# JacdacRp2040BrainEc30_124.net
KiCad netlist of a schematic drawn in Altium Designer
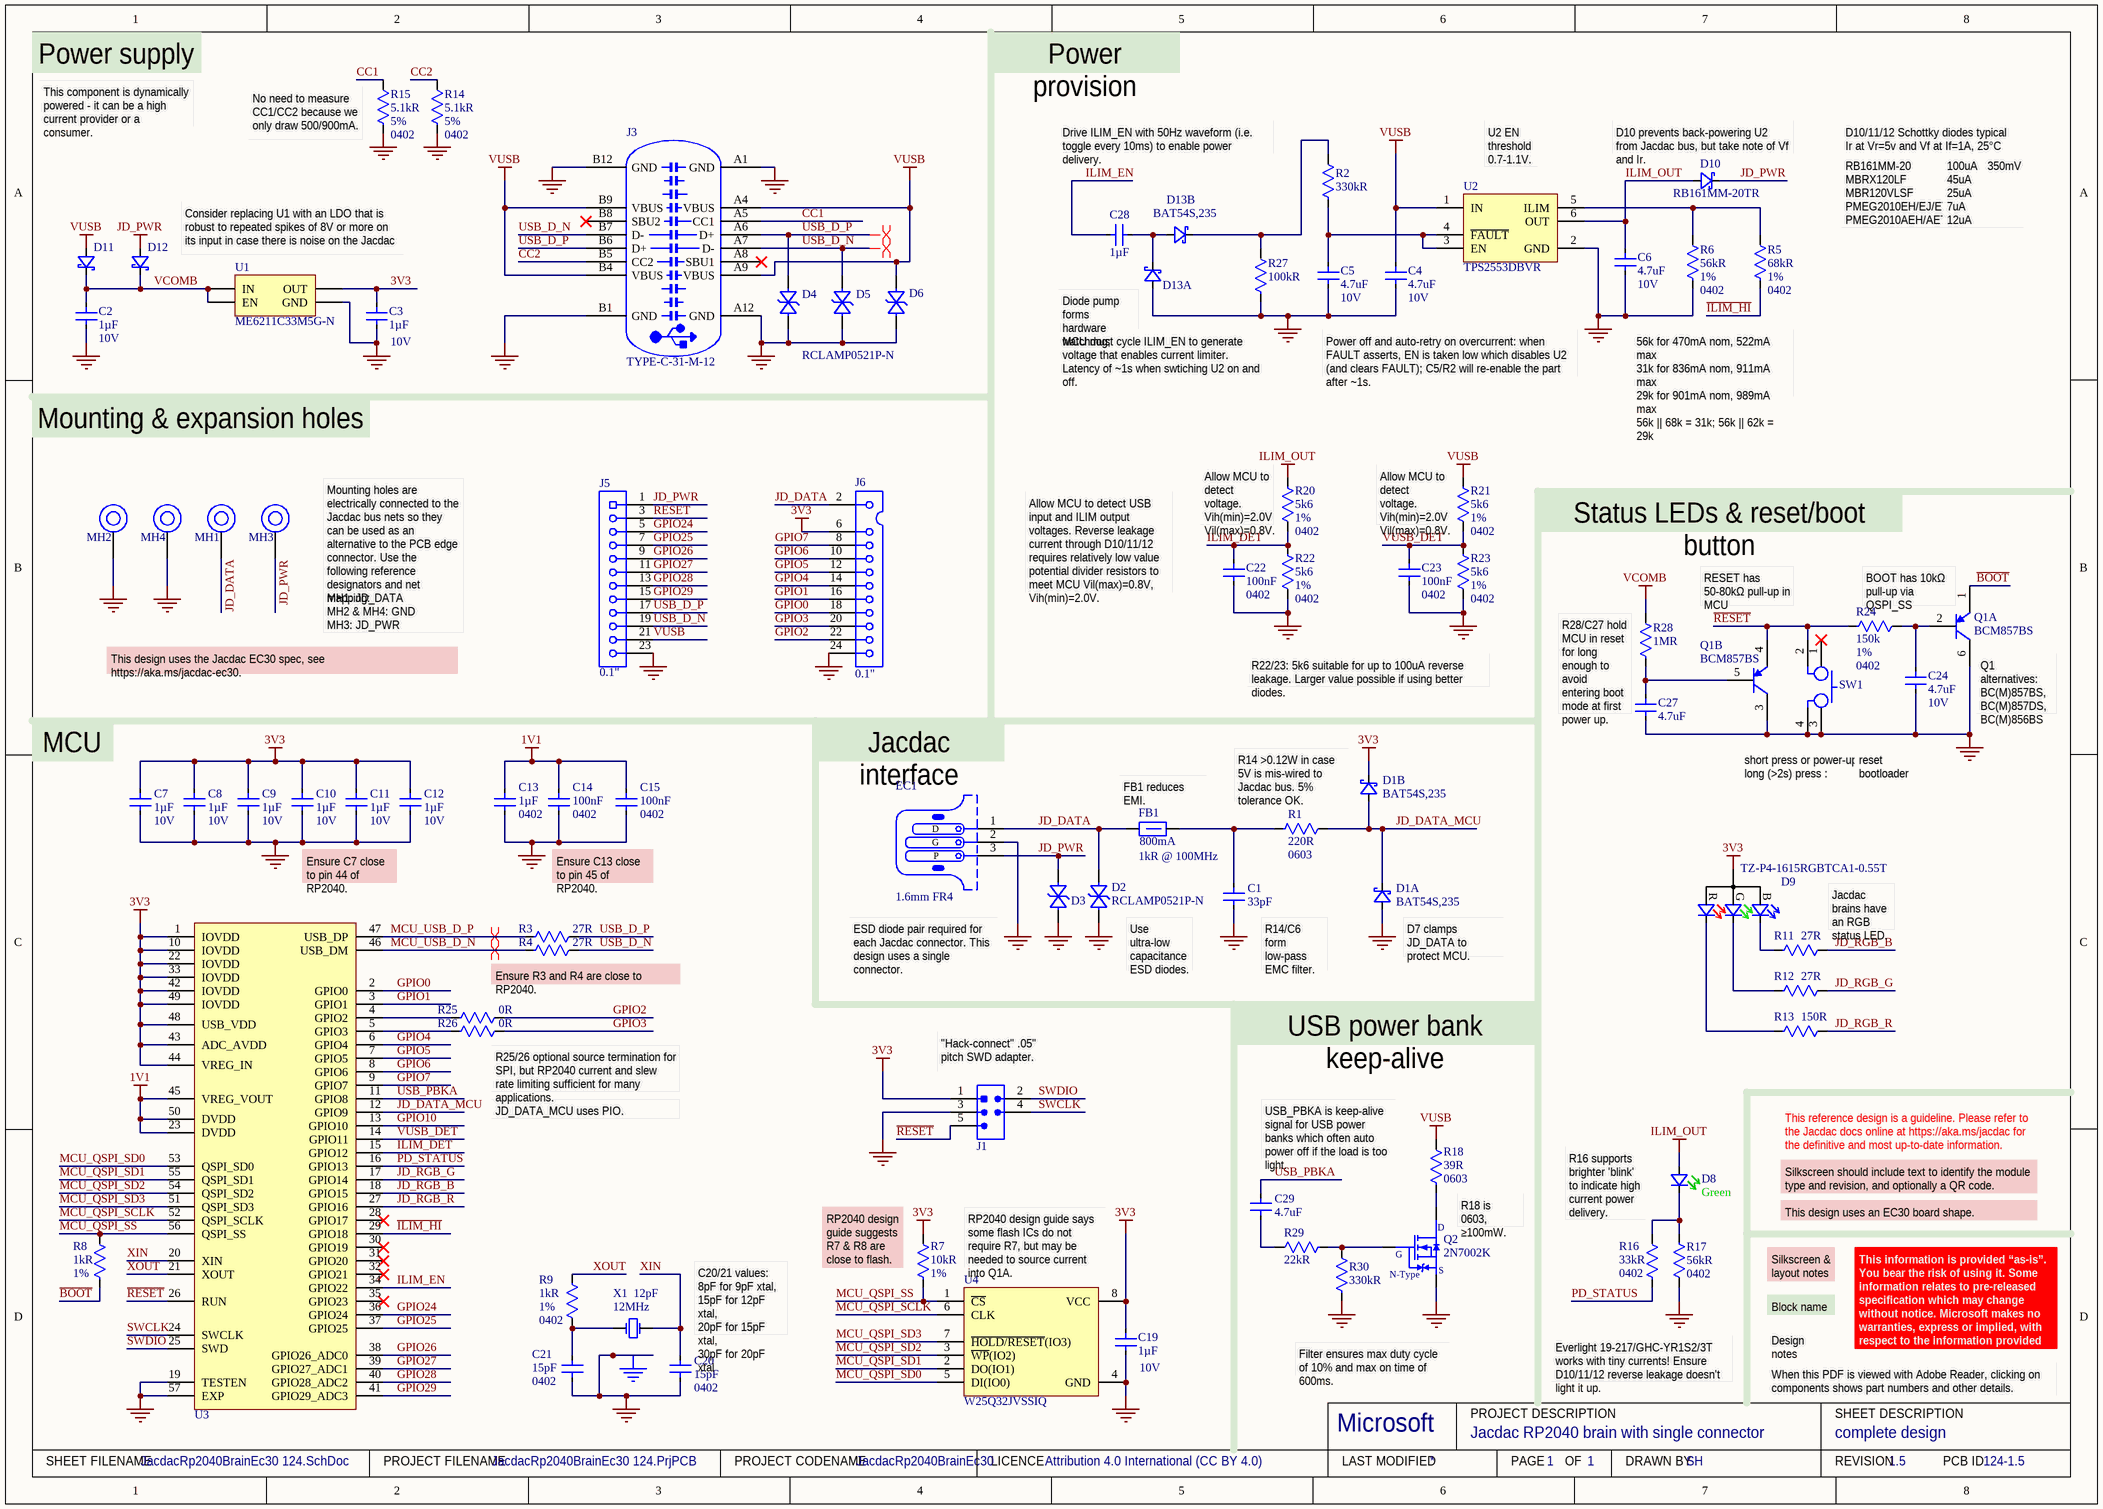
[diagram p0: JacdacRp2040BrainEc30 124.SchDoc]

(export (version "E")
  (design (tool "Eeschema 10.0.6"))
  (components
    (comp (ref "C1")
      (value "CL05C330JB51PNC")
      (footprint "C0402_0.55MM - without outline")
      (description "CAP CER 33PF 50V NP0 0402")
      (fields
        (field (name "MANUFACTURER") "Samsung")
        (field (name "TOLERANCE") "5%")
        (field (name "CAPACITANCE") "33pF")
        (field (name "CHECKED") "?")
        (field (name "CREATED") "DG")
      )
      (libsource (lib "Samsung") (part "CL05C330JB51PNC"))
    )
    (comp (ref "C2")
      (value "CL05A105KP5NNNC")
      (footprint "C0402_0.55MM - without outline")
      (description "CAP CER 1UF 10V X5R 0402")
      (fields
        (field (name "MANUFACTURER") "Samsung")
        (field (name "TOLERANCE") "10%")
        (field (name "CAPACITANCE") "1µF")
        (field (name "VOLTAGE RATING") "10V")
        (field (name "CREATED") "DG")
        (field (name "CHECKED") "?")
      )
      (libsource (lib "Samsung") (part "CL05A105KP5NNNC"))
    )
    (comp (ref "C3")
      (value "CL05A105KP5NNNC")
      (footprint "C0402_0.55MM - without outline")
      (description "CAP CER 1UF 10V X5R 0402")
      (fields
        (field (name "MANUFACTURER") "Samsung")
        (field (name "TOLERANCE") "10%")
        (field (name "CAPACITANCE") "1µF")
        (field (name "VOLTAGE RATING") "10V")
        (field (name "CREATED") "DG")
        (field (name "CHECKED") "?")
      )
      (libsource (lib "Samsung") (part "CL05A105KP5NNNC"))
    )
    (comp (ref "C4")
      (value "CL05A475MP5NRNC")
      (footprint "SAMSUNG-CAP-0402:C0402_0.55mm - without outline")
      (description "CAP CER 4.7UF 10V X5R 0402")
      (fields
        (field (name "MANUFACTURER") "Samsung")
        (field (name "TOLERANCE") "20%")
        (field (name "CAPACITANCE") "4.7uF")
        (field (name "VOLTAGE RATING") "10V")
        (field (name "CREATED BY") "D. Gakure")
        (field (name "CHECKED BY") "?")
      )
      (libsource (lib "Samsung") (part "CL05A475MP5NRNC"))
    )
    (comp (ref "C5")
      (value "CL05A475MP5NRNC")
      (footprint "SAMSUNG-CAP-0402:C0402_0.55mm - without outline")
      (description "CAP CER 4.7UF 10V X5R 0402")
      (fields
        (field (name "MANUFACTURER") "Samsung")
        (field (name "TOLERANCE") "20%")
        (field (name "CAPACITANCE") "4.7uF")
        (field (name "VOLTAGE RATING") "10V")
        (field (name "CREATED BY") "D. Gakure")
        (field (name "CHECKED BY") "?")
      )
      (libsource (lib "Samsung") (part "CL05A475MP5NRNC"))
    )
    (comp (ref "C6")
      (value "CL05A475MP5NRNC")
      (footprint "SAMSUNG-CAP-0402:C0402_0.55mm - without outline")
      (description "CAP CER 4.7UF 10V X5R 0402")
      (fields
        (field (name "MANUFACTURER") "Samsung")
        (field (name "TOLERANCE") "20%")
        (field (name "CAPACITANCE") "4.7uF")
        (field (name "VOLTAGE RATING") "10V")
        (field (name "CREATED BY") "D. Gakure")
        (field (name "CHECKED BY") "?")
      )
      (libsource (lib "Samsung") (part "CL05A475MP5NRNC"))
    )
    (comp (ref "C7")
      (value "CL05A105KP5NNNC")
      (footprint "C0402_0.55MM - without outline")
      (description "CAP CER 1UF 10V X5R 0402")
      (fields
        (field (name "MANUFACTURER") "Samsung")
        (field (name "TOLERANCE") "10%")
        (field (name "CAPACITANCE") "1µF")
        (field (name "VOLTAGE RATING") "10V")
        (field (name "CREATED") "DG")
        (field (name "CHECKED") "?")
      )
      (libsource (lib "Samsung") (part "CL05A105KP5NNNC"))
    )
    (comp (ref "C8")
      (value "CL05A105KP5NNNC")
      (footprint "C0402_0.55MM - without outline")
      (description "CAP CER 1UF 10V X5R 0402")
      (fields
        (field (name "MANUFACTURER") "Samsung")
        (field (name "TOLERANCE") "10%")
        (field (name "CAPACITANCE") "1µF")
        (field (name "VOLTAGE RATING") "10V")
        (field (name "CREATED") "DG")
        (field (name "CHECKED") "?")
      )
      (libsource (lib "Samsung") (part "CL05A105KP5NNNC"))
    )
    (comp (ref "C9")
      (value "CL05A105KP5NNNC")
      (footprint "C0402_0.55MM - without outline")
      (description "CAP CER 1UF 10V X5R 0402")
      (fields
        (field (name "MANUFACTURER") "Samsung")
        (field (name "TOLERANCE") "10%")
        (field (name "CAPACITANCE") "1µF")
        (field (name "VOLTAGE RATING") "10V")
        (field (name "CREATED") "DG")
        (field (name "CHECKED") "?")
      )
      (libsource (lib "Samsung") (part "CL05A105KP5NNNC"))
    )
    (comp (ref "C10")
      (value "CL05A105KP5NNNC")
      (footprint "C0402_0.55MM - without outline")
      (description "CAP CER 1UF 10V X5R 0402")
      (fields
        (field (name "MANUFACTURER") "Samsung")
        (field (name "TOLERANCE") "10%")
        (field (name "CAPACITANCE") "1µF")
        (field (name "VOLTAGE RATING") "10V")
        (field (name "CREATED") "DG")
        (field (name "CHECKED") "?")
      )
      (libsource (lib "Samsung") (part "CL05A105KP5NNNC"))
    )
    (comp (ref "C11")
      (value "CL05A105KP5NNNC")
      (footprint "C0402_0.55MM - without outline")
      (description "CAP CER 1UF 10V X5R 0402")
      (fields
        (field (name "MANUFACTURER") "Samsung")
        (field (name "TOLERANCE") "10%")
        (field (name "CAPACITANCE") "1µF")
        (field (name "VOLTAGE RATING") "10V")
        (field (name "CREATED") "DG")
        (field (name "CHECKED") "?")
      )
      (libsource (lib "Samsung") (part "CL05A105KP5NNNC"))
    )
    (comp (ref "C12")
      (value "CL05A105KP5NNNC")
      (footprint "C0402_0.55MM - without outline")
      (description "CAP CER 1UF 10V X5R 0402")
      (fields
        (field (name "MANUFACTURER") "Samsung")
        (field (name "TOLERANCE") "10%")
        (field (name "CAPACITANCE") "1µF")
        (field (name "VOLTAGE RATING") "10V")
        (field (name "CREATED") "DG")
        (field (name "CHECKED") "?")
      )
      (libsource (lib "Samsung") (part "CL05A105KP5NNNC"))
    )
    (comp (ref "C13")
      (value "CL05A105KP5NNNC")
      (footprint "C0402_0.55MM - without outline")
      (description "CAP CER 1UF 10V X5R 0402")
      (fields
        (field (name "MANUFACTURER") "Samsung")
        (field (name "CASE/PACKAGE") "0402")
        (field (name "TOLERANCE") "10%")
        (field (name "CAPACITANCE") "1µF")
        (field (name "CREATED") "DG")
        (field (name "CHECKED") "?")
      )
      (libsource (lib "Samsung") (part "CL05A105KP5NNNC"))
    )
    (comp (ref "C14")
      (value "CL05B104KP5NNNC")
      (footprint "SAMSUNG-CAP-0402:C0402_0.55MM - without outline")
      (description "CAP CER 0.1UF 10V X7R 0402")
      (fields
        (field (name "MANUFACTURER") "Samsung")
        (field (name "TOLERANCE") "10%")
        (field (name "CAPACITANCE") "100nF")
        (field (name "CASE CODE (IMPERIAL)") "0402")
        (field (name "CREATED") "DG")
        (field (name "CHECKED") "?")
      )
      (libsource (lib "Samsung") (part "CL05B104KP5NNNC"))
    )
    (comp (ref "C15")
      (value "CL05B104KP5NNNC")
      (footprint "SAMSUNG-CAP-0402:C0402_0.55MM - without outline")
      (description "CAP CER 0.1UF 10V X7R 0402")
      (fields
        (field (name "MANUFACTURER") "Samsung")
        (field (name "TOLERANCE") "10%")
        (field (name "CAPACITANCE") "100nF")
        (field (name "CASE CODE (IMPERIAL)") "0402")
        (field (name "CREATED") "DG")
        (field (name "CHECKED") "?")
      )
      (libsource (lib "Samsung") (part "CL05B104KP5NNNC"))
    )
    (comp (ref "C19")
      (value "CL05A105KP5NNNC")
      (footprint "C0402_0.55MM - without outline")
      (description "CAP CER 1UF 10V X5R 0402")
      (fields
        (field (name "MANUFACTURER") "Samsung")
        (field (name "TOLERANCE") "10%")
        (field (name "CAPACITANCE") "1µF")
        (field (name "VOLTAGE RATING") "10V")
        (field (name "CREATED") "DG")
        (field (name "CHECKED") "?")
      )
      (libsource (lib "Samsung") (part "CL05A105KP5NNNC"))
    )
    (comp (ref "C20")
      (value "CL05C150JB5NNNC")
      (footprint "C0402_0.55MM - without outline")
      (description "CAP CER 15PF 50V C0G/NP0 0402")
      (fields
        (field (name "MANUFACTURER") "Samsung")
        (field (name "TOLERANCE") "5%")
        (field (name "CAPACITANCE") "15pF")
        (field (name "CASE/PACKAGE") "0402")
      )
      (libsource (lib "Samsung") (part "CL05C150JB5NNNC"))
    )
    (comp (ref "C21")
      (value "CL05C150JB5NNNC")
      (footprint "C0402_0.55MM - without outline")
      (description "CAP CER 15PF 50V C0G/NP0 0402")
      (fields
        (field (name "MANUFACTURER") "Samsung")
        (field (name "TOLERANCE") "5%")
        (field (name "CAPACITANCE") "15pF")
        (field (name "CASE/PACKAGE") "0402")
      )
      (libsource (lib "Samsung") (part "CL05C150JB5NNNC"))
    )
    (comp (ref "C22")
      (value "CL05B104KP5NNNC")
      (footprint "SAMSUNG-CAP-0402:C0402_0.55MM - without outline")
      (description "CAP CER 0.1UF 10V X7R 0402")
      (fields
        (field (name "MANUFACTURER") "Samsung")
        (field (name "TOLERANCE") "10%")
        (field (name "CAPACITANCE") "100nF")
        (field (name "CASE CODE (IMPERIAL)") "0402")
        (field (name "CREATED") "DG")
        (field (name "CHECKED") "?")
      )
      (libsource (lib "Samsung") (part "CL05B104KP5NNNC"))
    )
    (comp (ref "C23")
      (value "CL05B104KP5NNNC")
      (footprint "SAMSUNG-CAP-0402:C0402_0.55MM - without outline")
      (description "CAP CER 0.1UF 10V X7R 0402")
      (fields
        (field (name "MANUFACTURER") "Samsung")
        (field (name "TOLERANCE") "10%")
        (field (name "CAPACITANCE") "100nF")
        (field (name "CASE CODE (IMPERIAL)") "0402")
        (field (name "CREATED") "DG")
        (field (name "CHECKED") "?")
      )
      (libsource (lib "Samsung") (part "CL05B104KP5NNNC"))
    )
    (comp (ref "C24")
      (value "CL05A475MP5NRNC")
      (footprint "SAMSUNG-CAP-0402:C0402_0.55mm - without outline")
      (description "CAP CER 4.7UF 10V X5R 0402")
      (fields
        (field (name "MANUFACTURER") "Samsung")
        (field (name "TOLERANCE") "20%")
        (field (name "CAPACITANCE") "4.7uF")
        (field (name "VOLTAGE RATING") "10V")
        (field (name "CREATED BY") "D. Gakure")
        (field (name "CHECKED BY") "?")
      )
      (libsource (lib "Samsung") (part "CL05A475MP5NRNC"))
    )
    (comp (ref "C27")
      (value "CL05A475MP5NRNC")
      (footprint "SAMSUNG-CAP-0402:C0402_0.55mm - without outline")
      (description "CAP CER 4.7UF 10V X5R 0402")
      (fields
        (field (name "MANUFACTURER") "Samsung")
        (field (name "TOLERANCE") "20%")
        (field (name "CAPACITANCE") "4.7uF")
        (field (name "CREATED BY") "D. Gakure")
        (field (name "CHECKED BY") "?")
      )
      (libsource (lib "Samsung") (part "CL05A475MP5NRNC"))
    )
    (comp (ref "C28")
      (value "CL05A105KP5NNNC")
      (footprint "SAMSUNG-CAP-0402:C0402_0.55MM - without outline")
      (description "CAP CER 1UF 10V X5R 0402")
      (fields
        (field (name "MANUFACTURER") "Samsung")
        (field (name "TOLERANCE") "10%")
        (field (name "CAPACITANCE") "1µF")
        (field (name "CREATED") "DG")
        (field (name "CHECKED") "?")
      )
      (libsource (lib "Samsung") (part "CL05A105KP5NNNC"))
    )
    (comp (ref "C29")
      (value "CL05A475MP5NRNC")
      (footprint "SAMSUNG-CAP-0402:C0402_0.55mm - without outline")
      (description "CAP CER 4.7UF 10V X5R 0402")
      (fields
        (field (name "MANUFACTURER") "Samsung")
        (field (name "TOLERANCE") "20%")
        (field (name "CAPACITANCE") "4.7uF")
        (field (name "CREATED BY") "D. Gakure")
        (field (name "CHECKED BY") "?")
      )
      (libsource (lib "Samsung") (part "CL05A475MP5NRNC"))
    )
    (comp (ref "D1")
      (value "BAT54S")
      (footprint "NXP-BAT54S-TO-236AB - without outline")
      (description "DIODE ARRAY SCHOTTKY 30V SOT23")
      (fields (field (name "MANUFACTURER") "Nexperia") (field (name "MANUFACTURER PART NUMBER") "BAT54S,235"))
      (libsource (lib "NXP") (part "BAT54S"))
    )
    (comp (ref "D2")
      (value "RCLAMP0521P-N")
      (footprint "0402:TVS 0402 - L")
      (description "Bidirectional 5V (Max) 6V 16V 3.5A (8/20us) 0402 TVS RoHS")
      (fields
        (field (name "MANUFACTURER") "Born Semiconductor")
        (field (name "MANUFACTURER PART NUMBER") "RCLAMP0521P-N")
        (field (name "CREATED BY") "D Gakure")
        (field (name "CHECKED BY") "?")
      )
      (libsource (lib "BornSemiconductor") (part "RCLAMP0521P-N"))
    )
    (comp (ref "D3")
      (value "RCLAMP0521P-N")
      (footprint "0402:TVS 0402 - L")
      (description "Bidirectional 5V (Max) 6V 16V 3.5A (8/20us) 0402 TVS RoHS")
      (fields
        (field (name "MANUFACTURER") "Born Semiconductor")
        (field (name "CREATED BY") "D Gakure")
        (field (name "CHECKED BY") "?")
      )
      (libsource (lib "BornSemiconductor") (part "RCLAMP0521P-N"))
    )
    (comp (ref "D4")
      (value "RCLAMP0521P-N")
      (footprint "0402:TVS 0402 - L")
      (description "Bidirectional 5V (Max) 6V 16V 3.5A (8/20us) 0402 TVS RoHS")
      (fields
        (field (name "MANUFACTURER") "Born Semiconductor")
        (field (name "CREATED BY") "D Gakure")
        (field (name "CHECKED BY") "?")
      )
      (libsource (lib "BornSemiconductor") (part "RCLAMP0521P-N"))
    )
    (comp (ref "D5")
      (value "RCLAMP0521P-N")
      (footprint "0402:TVS 0402 - L")
      (description "Bidirectional 5V (Max) 6V 16V 3.5A (8/20us) 0402 TVS RoHS")
      (fields
        (field (name "MANUFACTURER") "Born Semiconductor")
        (field (name "CREATED BY") "D Gakure")
        (field (name "CHECKED BY") "?")
      )
      (libsource (lib "BornSemiconductor") (part "RCLAMP0521P-N"))
    )
    (comp (ref "D6")
      (value "RCLAMP0521P-N")
      (footprint "0402:TVS 0402 - L")
      (description "Bidirectional 5V (Max) 6V 16V 3.5A (8/20us) 0402 TVS RoHS")
      (fields
        (field (name "MANUFACTURER") "Born Semiconductor")
        (field (name "MANUFACTURER PART NUMBER") "RCLAMP0521P-N")
        (field (name "CREATED BY") "D Gakure")
        (field (name "CHECKED BY") "?")
      )
      (libsource (lib "BornSemiconductor") (part "RCLAMP0521P-N"))
    )
    (comp (ref "D8")
      (value "~")
      (footprint "Green_0603:0603 Green")
      (description "LED GREEN DIFFUSED 0603 SMD")
      (fields
        (field (name "MANUFACTURER") "Everlight Elec")
        (field (name "MANUFACTURER PART NUMBER") "19-217/GHC-YR1S2/3T")
        (field (name "COLOUR") "Green")
      )
      (libsource (lib "EverlightElec") (part "19-217/GHC-YR1S2/3T"))
    )
    (comp (ref "D9")
      (value "TZ-P4-1615RGBTCA1-0.55T")
      (footprint "TUOZHAN-TZ-P4-1615RGBTCA1-0.55T:TZ-P4-1615RGBTCA1-0.55T")
      (description "1615 Light Emitting Diodes (LED) RoHS")
      (fields
        (field (name "MANUFACTURER") "TUOZHAN")
        (field (name "CREATED BY") "D. Gakure")
        (field (name "CHECKED BY") "?")
      )
      (libsource (lib "Tuozhan") (part "TZ-P4-1615RGBTCA1-0.55T"))
    )
    (comp (ref "D10")
      (value "RB161MM-20TR")
      (footprint "SOD-123F:SOD-123F - without outline")
      (description "ROHM - RB161MM-20TR - Schottky-Gleichrichterdiode, 20 V, 1 A, Einfach, SOD-123FL, 2 Pin(s), 350 mV")
      (fields (field (name "MANUFACTURER") "Rohm") (field (name "MANUFACTURER PART NUMBER") "RB161MM-20TR"))
      (libsource (lib "Rohm") (part "RB161MM-20TR"))
    )
    (comp (ref "D11")
      (value "RB161MM-20TR")
      (footprint "SOD-123F:SOD-123F - without outline")
      (description "ROHM - RB161MM-20TR - Schottky-Gleichrichterdiode, 20 V, 1 A, Einfach, SOD-123FL, 2 Pin(s), 350 mV")
      (fields (field (name "MANUFACTURER") "Rohm"))
      (libsource (lib "Rohm") (part "RB161MM-20TR"))
    )
    (comp (ref "D12")
      (value "RB161MM-20TR")
      (footprint "SOD-123F:SOD-123F - without outline")
      (description "ROHM - RB161MM-20TR - Schottky-Gleichrichterdiode, 20 V, 1 A, Einfach, SOD-123FL, 2 Pin(s), 350 mV")
      (fields (field (name "MANUFACTURER") "Rohm"))
      (libsource (lib "Rohm") (part "RB161MM-20TR"))
    )
    (comp (ref "D13")
      (value "BAT54S")
      (footprint "NXP-BAT54S:NXP-BAT54S-TO-236AB - without outline")
      (description "DIODE ARRAY SCHOTTKY 30V SOT23")
      (fields (field (name "MANUFACTURER") "Nexperia") (field (name "MANUFACTURER PART NUMBER") "BAT54S,235"))
      (libsource (lib "NXP") (part "BAT54S"))
    )
    (comp (ref "EC1")
      (value "Jacdac edge connector")
      (footprint "JACDAC_edge_connector:JACDAC_EDGE_CONNECTOR_NO_TRACES_3D_PADS")
      (description "3 pin Jacdac edge connector 1.27mm pitch")
      (fields
        (field (name "MANUFACTURER PART NUMBER") "n/a")
        (field (name "PCB TYPE") "1.6mm FR4")
        (field (name "CREATED BY") "D. Gakure & S. Hodges")
      )
      (libsource (lib "generic-con") (part "Jacdac edge connector"))
    )
    (comp (ref "FB1")
      (value "TDK MPZ1608S102ATA00")
      (footprint "TDK MPZ1608 0.8mm - without outline")
      (description "0603 1k@100MHz 0.8A chip")
      (fields
        (field (name "TOLERANCE") "25%")
        (field (name "MANUFACTURER") "TDK")
        (field (name "CURRENT RATING") "800mA")
        (field (name "IMPEDANCE") "1kR @ 100MHz")
      )
      (libsource (lib "TDK") (part "TDK MPZ1608S102ATA00"))
    )
    (comp (ref "J1")
      (value "Hack Connect Mini 1.27 mm pitch 2-row")
      (footprint "HACK_CONNECT_MINI_5_X_1_27")
      (libsource (lib "generic-con") (part "HACK_CONNECT_MINI"))
    )
    (comp (ref "J3")
      (value "~")
      (footprint "TYPE-C-31-M-12")
      (description "USB - Type C Female 16 USB Connectors RoHS")
      (fields
        (field (name "MANUFACTURER") "Korean Hroparts Elec")
        (field (name "MANUFACTURER PART NUMBER") "TYPE-C-31-M-12")
      )
      (libsource (lib "KoreanHropartsElec") (part "TYPE-C-31-M-12"))
    )
    (comp (ref "J5")
      (value "0.1\"")
      (footprint "generic-con-0.1inch:Jacdac EC30 stamp holes 30mm bottom")
      (description "2.54mm, 12x1 way, vertical, TH")
      (fields (field (name "MANUFACTURER") "Generic") (field (name "MANUFACTURER PART NUMBER") "TBD"))
      (libsource (lib "generic-con") (part "Jacdac EC30 stamp holes 30mm bottom"))
    )
    (comp (ref "J6")
      (value "0.1\"")
      (footprint "generic-con-0.1inch:Jacdac EC30 stamp holes 30mm top")
      (description "2.54mm, 12x1 way, vertical, TH")
      (fields (field (name "MANUFACTURER") "Generic") (field (name "MANUFACTURER PART NUMBER") "TBD"))
      (libsource (lib "generic-con") (part "Jacdac EC30 stamp holes 30mm top"))
    )
    (comp (ref "MH1")
      (value "MH_7.0MMK_4.4MMC_3.1MMD_PTH")
      (footprint "MH_7.0MMK_4.4MMC_3.1MMD_PTH:MH_7.0MMK_4.4MMC_3.1MMD_PTH-SILK_D")
      (description "Mounting Hole 7.0mm keepout, 4.4mm annualar ring and 3.1mm Drill PTH")
      (libsource (lib "generic") (part "MH_7.0MMK_4.4MMC_3.1MMD_PTH"))
    )
    (comp (ref "MH2")
      (value "MH_7.0MMK_4.4MMC_3.1MMD_PTH")
      (footprint "MH_7.0MMK_4.4MMC_3.1MMD_PTH:MH_7.0MMK_4.4MMC_3.1MMD_PTH-SILK_G")
      (description "Mounting Hole 7.0mm keepout, 4.4mm annualar ring and 3.1mm Drill PTH")
      (libsource (lib "generic") (part "MH_7.0MMK_4.4MMC_3.1MMD_PTH"))
    )
    (comp (ref "MH3")
      (value "MH_7.0MMK_4.4MMC_3.1MMD_PTH")
      (footprint "MH_7.0MMK_4.4MMC_3.1MMD_PTH:MH_7.0MMK_4.4MMC_3.1MMD_PTH-SILK_P")
      (description "Mounting Hole 7.0mm keepout, 4.4mm annualar ring and 3.1mm Drill PTH")
      (libsource (lib "generic") (part "MH_7.0MMK_4.4MMC_3.1MMD_PTH"))
    )
    (comp (ref "MH4")
      (value "MH_7.0MMK_4.4MMC_3.1MMD_PTH")
      (footprint "MH_7.0MMK_4.4MMC_3.1MMD_PTH:MH_7.0MMK_4.4MMC_3.1MMD_PTH-SILK_G")
      (description "Mounting Hole 7.0mm keepout, 4.4mm annualar ring and 3.1mm Drill PTH")
      (libsource (lib "generic") (part "MH_7.0MMK_4.4MMC_3.1MMD_PTH"))
    )
    (comp (ref "Q1")
      (value "BCM857BS")
      (footprint "NXP-SOT363:GENERIC-SOT363-NO-SILK")
      (description "BJT ARRAY, DUAL PNP, -45V, -100MA, 6-SOT-363")
      (fields
        (field (name "MANUFACTURER") "NXP Semiconductors")
        (field (name "MANUFACTURER PART NUMBER") "BCM857BS,115")
      )
      (libsource (lib "NXP") (part "BCM857BS,115-whitesch"))
    )
    (comp (ref "Q2")
      (value "2N7002K")
      (footprint "ON_SEMI-SOT23:SOT23-ONS")
      (description "MOSFET Transistor, N Channel, 300 mA, 60 V, 2 ohm, 10 V, 2.5 V")
      (fields
        (field (name "MANUFACTURER") "ON Semiconductor / Fairchild")
        (field (name "MANUFACTURER PART NUMBER") "2N7002K")
        (field (name "VOLTAGE") "60V")
        (field (name "CHECKED BY") "?")
        (field (name "CREATED BY") "D. Gakure")
      )
      (libsource (lib "OnSemiconductor") (part "2N7002K"))
    )
    (comp (ref "R1")
      (value "~")
      (footprint "YAGEO-0603:RC0603")
      (description "Res Thick Film 0603 220 Ohm 1% 0.1W(1/10W) ±100ppm/°C Pad SMD T/R")
      (fields
        (field (name "MANUFACTURER") "Yageo")
        (field (name "MANUFACTURER PART NUMBER") "RC0603FR-07220RL")
        (field (name "RESISTANCE") "220R")
        (field (name "CASE/PACKAGE") "0603")
      )
      (libsource (lib "Yageo") (part "RC0603FR-07220RL"))
    )
    (comp (ref "R2")
      (value "RC0402FR-07330KL")
      (footprint "YAGEO-0402:R0402 - without outline")
      (description "RES SMD 330K OHM 1% 1/16W 0402")
      (fields
        (field (name "MANUFACTURER") "Yageo")
        (field (name "RESISTANCE") "330kR")
        (field (name "TOLERANCE") "1%")
        (field (name "CREATED BY") "D Gakure")
        (field (name "CHECKED BY") "?")
      )
      (libsource (lib "Yageo") (part "RC0402FR-07330KL"))
    )
    (comp (ref "R3")
      (value "RC0402FR-0727RL")
      (footprint "R0402 - Without outline")
      (description "RES SMD 27 OHM 1% 1/16W 0402")
      (fields
        (field (name "MANUFACTURER") "Yageo")
        (field (name "TOLERANCE") "1%")
        (field (name "RESISTANCE") "27R")
      )
      (libsource (lib "Yageo") (part "RC0402FR-0727RL"))
    )
    (comp (ref "R4")
      (value "RC0402FR-0727RL")
      (footprint "R0402 - Without outline")
      (description "RES SMD 27 OHM 1% 1/16W 0402")
      (fields
        (field (name "MANUFACTURER") "Yageo")
        (field (name "TOLERANCE") "1%")
        (field (name "RESISTANCE") "27R")
      )
      (libsource (lib "Yageo") (part "RC0402FR-0727RL"))
    )
    (comp (ref "R5")
      (value "RC0402FR-0768KL")
      (footprint "YAGEO-0402:R0402 - Without outline")
      (description "RES SMD 68K OHM 1% 1/16W 0402")
      (fields
        (field (name "MANUFACTURER") "Yageo")
        (field (name "RESISTANCE") "68kR")
        (field (name "TOLERANCE") "1%")
        (field (name "CASE/PACKAGE") "0402")
        (field (name "CREATED BY") "DG")
        (field (name "CHECKED BY") "?")
      )
      (libsource (lib "Yageo") (part "RC0402FR-0768KL"))
    )
    (comp (ref "R6")
      (value "RC0402FR-0756KL")
      (footprint "YAGEO-0402:R0402 - Without outline")
      (description "RES SMD 56K OHM 1% 1/16W 0402")
      (fields
        (field (name "MANUFACTURER") "Yageo")
        (field (name "RESISTANCE") "56kR")
        (field (name "TOLERANCE") "1%")
        (field (name "CASE/PACKAGE") "0402")
        (field (name "CREATED BY") "DG")
        (field (name "CHECKED BY") "?")
      )
      (libsource (lib "Yageo") (part "RC0402FR-0756KL"))
    )
    (comp (ref "R7")
      (value "~")
      (footprint "YAGEO-0402:R0402 - Without outline")
      (description "RES SMD 10K OHM 1% 1/16W 0402")
      (fields
        (field (name "MANUFACTURER") "Yageo")
        (field (name "MANUFACTURER PART NUMBER") "RC0402FR-0710KL")
        (field (name "RESISTANCE") "10kR")
        (field (name "TOLERANCE") "1%")
        (field (name "CHECKED") "?")
        (field (name "CREATED") "DG")
      )
      (libsource (lib "Yageo") (part "RC0402FR-0710KL"))
    )
    (comp (ref "R8")
      (value "RC0402FR-071KL")
      (footprint "R0402 - Without outline")
      (description "RES SMD 1K OHM 1% 1/16W 0402")
      (fields
        (field (name "MANUFACTURER") "Yageo")
        (field (name "RESISTANCE") "1kR")
        (field (name "TOLERANCE") "1%")
        (field (name "CREATED") "D.G")
        (field (name "CHECKED") "?")
      )
      (libsource (lib "Yageo") (part "RC0402FR-071KL"))
    )
    (comp (ref "R9")
      (value "RC0402FR-071KL")
      (footprint "R0402 - Without outline")
      (description "RES SMD 1K OHM 1% 1/16W 0402")
      (fields
        (field (name "MANUFACTURER") "Yageo")
        (field (name "RESISTANCE") "1kR")
        (field (name "TOLERANCE") "1%")
        (field (name "CASE CODE (IMPERIAL)") "0402")
        (field (name "CREATED") "D.G")
        (field (name "CHECKED") "?")
      )
      (libsource (lib "Yageo") (part "RC0402FR-071KL"))
    )
    (comp (ref "R11")
      (value "RC0402FR-0727RL")
      (footprint "R0402 - Without outline")
      (description "RES SMD 27 OHM 1% 1/16W 0402")
      (fields
        (field (name "MANUFACTURER") "Yageo")
        (field (name "TOLERANCE") "1%")
        (field (name "RESISTANCE") "27R")
      )
      (libsource (lib "Yageo") (part "RC0402FR-0727RL"))
    )
    (comp (ref "R12")
      (value "RC0402FR-0727RL")
      (footprint "R0402 - Without outline")
      (description "RES SMD 27 OHM 1% 1/16W 0402")
      (fields
        (field (name "MANUFACTURER") "Yageo")
        (field (name "TOLERANCE") "1%")
        (field (name "RESISTANCE") "27R")
      )
      (libsource (lib "Yageo") (part "RC0402FR-0727RL"))
    )
    (comp (ref "R13")
      (value "RC0402FR-07150RL")
      (footprint "R0402 - Without outline")
      (description "RES SMD 150 OHM 1% 1/16W 0402")
      (fields
        (field (name "MANUFACTURER") "Yageo")
        (field (name "RESISTANCE") "150R")
        (field (name "TOLERANCE") "1%")
        (field (name "CREATED BY") "D. Gakure")
        (field (name "CHECKED BY") "?")
      )
      (libsource (lib "Yageo") (part "RC0402FR-07150RL"))
    )
    (comp (ref "R14")
      (value "RC0402JR-075K1L")
      (footprint "R0402 - Without outline")
      (description "RES SMD 5.1K OHM 5% 1/16W 0402")
      (fields
        (field (name "MANUFACTURER") "Yageo")
        (field (name "RESISTANCE") "5.1kR")
        (field (name "TOLERANCE") "5%")
        (field (name "CASE CODE (IMPERIAL)") "0402")
        (field (name "CREATED BY") "D. Gakure")
        (field (name "CHECKED BY") "?")
      )
      (libsource (lib "Yageo") (part "RC0402JR-075K1L"))
    )
    (comp (ref "R15")
      (value "RC0402JR-075K1L")
      (footprint "R0402 - Without outline")
      (description "RES SMD 5.1K OHM 5% 1/16W 0402")
      (fields
        (field (name "MANUFACTURER") "Yageo")
        (field (name "RESISTANCE") "5.1kR")
        (field (name "TOLERANCE") "5%")
        (field (name "CASE CODE (IMPERIAL)") "0402")
        (field (name "CREATED BY") "D. Gakure")
        (field (name "CHECKED BY") "?")
      )
      (libsource (lib "Yageo") (part "RC0402JR-075K1L"))
    )
    (comp (ref "R16")
      (value "RC0402FR-0733KL")
      (footprint "YAGEO-0402:R0402 - Without outline")
      (description "RES SMD 33K OHM 1% 1/16W 0402")
      (fields
        (field (name "MANUFACTURER") "Yageo")
        (field (name "RESISTANCE") "33kR")
        (field (name "TOLERANCE") "1%")
        (field (name "CASE CODE (IMPERIAL)") "0402")
        (field (name "CHECKED BY") "?")
      )
      (libsource (lib "Yageo") (part "RC0402FR-0733KL"))
    )
    (comp (ref "R17")
      (value "RC0402FR-0756KL")
      (footprint "YAGEO-0402:R0402 - Without outline")
      (description "RES SMD 56K OHM 1% 1/16W 0402")
      (fields
        (field (name "MANUFACTURER") "Yageo")
        (field (name "RESISTANCE") "56kR")
        (field (name "TOLERANCE") "1%")
        (field (name "CASE/PACKAGE") "0402")
        (field (name "CREATED BY") "DG")
        (field (name "CHECKED BY") "?")
      )
      (libsource (lib "Yageo") (part "RC0402FR-0756KL"))
    )
    (comp (ref "R18")
      (value "RC0603FR-0739RL")
      (footprint "YAGEO-0603:RC0603-M")
      (description "RES SMD 39 OHM 1% 1/10W 0603")
      (fields
        (field (name "MANUFACTURER") "Yageo")
        (field (name "RESISTANCE") "39R")
        (field (name "TOLERANCE") "1%")
        (field (name "CASE CODE (IMPERIAL)") "0603")
        (field (name "CREATED BY") "D. Gakure")
      )
      (libsource (lib "Yageo") (part "RC0603FR-0739RL"))
    )
    (comp (ref "R20")
      (value "~")
      (footprint "YAGEO-0402:R0402 - Without outline")
      (description "RES SMD 5K6 OHM 1% 1/16W 0402")
      (fields
        (field (name "MANUFACTURER PART NUMBER") "RC0402FR-075K6L")
        (field (name "MANUFACTURER") "Yageo")
        (field (name "RESISTANCE") "5k6")
        (field (name "TOLERANCE") "1%")
        (field (name "CASE CODE (IMPERIAL)") "0402")
        (field (name "CHECKED") "?")
      )
      (libsource (lib "Yageo") (part "RC0402FR-075K6L"))
    )
    (comp (ref "R21")
      (value "~")
      (footprint "YAGEO-0402:R0402 - Without outline")
      (description "RES SMD 5K6 OHM 1% 1/16W 0402")
      (fields
        (field (name "MANUFACTURER PART NUMBER") "RC0402FR-075K6L")
        (field (name "MANUFACTURER") "Yageo")
        (field (name "RESISTANCE") "5k6")
        (field (name "TOLERANCE") "1%")
        (field (name "CASE CODE (IMPERIAL)") "0402")
        (field (name "CHECKED") "?")
      )
      (libsource (lib "Yageo") (part "RC0402FR-075K6L"))
    )
    (comp (ref "R22")
      (value "~")
      (footprint "YAGEO-0402:R0402 - Without outline")
      (description "RES SMD 5K6 OHM 1% 1/16W 0402")
      (fields
        (field (name "MANUFACTURER PART NUMBER") "RC0402FR-075K6L")
        (field (name "MANUFACTURER") "Yageo")
        (field (name "RESISTANCE") "5k6")
        (field (name "TOLERANCE") "1%")
        (field (name "CASE CODE (IMPERIAL)") "0402")
        (field (name "CHECKED") "?")
      )
      (libsource (lib "Yageo") (part "RC0402FR-075K6L"))
    )
    (comp (ref "R23")
      (value "~")
      (footprint "YAGEO-0402:R0402 - Without outline")
      (description "RES SMD 5K6 OHM 1% 1/16W 0402")
      (fields
        (field (name "MANUFACTURER PART NUMBER") "RC0402FR-075K6L")
        (field (name "MANUFACTURER") "Yageo")
        (field (name "RESISTANCE") "5k6")
        (field (name "TOLERANCE") "1%")
        (field (name "CASE CODE (IMPERIAL)") "0402")
        (field (name "CHECKED") "?")
      )
      (libsource (lib "Yageo") (part "RC0402FR-075K6L"))
    )
    (comp (ref "R24")
      (value "RC0402FR-07150KL")
      (footprint "YAGEO-0402:R0402 - Without outline")
      (description "RES SMD 150K OHM 1% 1/16W 0402")
      (fields
        (field (name "MANUFACTURER") "Yageo")
        (field (name "RESISTANCE") "150k")
        (field (name "TOLERANCE") "1%")
        (field (name "CASE/PACKAGE") "0402")
        (field (name "CREATED BY") "DG")
        (field (name "CHECKED BY") "?")
      )
      (libsource (lib "Yageo") (part "RC0402FR-07150KL"))
    )
    (comp (ref "R25")
      (value "RC0402JR-070RL")
      (footprint "YAGEO-0402:R0402 - Without outline")
      (description "RES SMD 0 OHM JUMPER 1/16W 0402")
      (fields
        (field (name "MANUFACTURER") "Yageo")
        (field (name "TOLERANCE") "5%")
        (field (name "RESISTANCE") "0R")
        (field (name "CREATED") "DG")
        (field (name "CHECKED") "?")
      )
      (libsource (lib "Yageo") (part "RC0402JR-070RL"))
    )
    (comp (ref "R26")
      (value "RC0402JR-070RL")
      (footprint "YAGEO-0402:R0402 - Without outline")
      (description "RES SMD 0 OHM JUMPER 1/16W 0402")
      (fields
        (field (name "MANUFACTURER") "Yageo")
        (field (name "TOLERANCE") "5%")
        (field (name "RESISTANCE") "0R")
        (field (name "CREATED") "DG")
        (field (name "CHECKED") "?")
      )
      (libsource (lib "Yageo") (part "RC0402JR-070RL"))
    )
    (comp (ref "R27")
      (value "RC0402FR-07100KL")
      (footprint "YAGEO-0402:R0402 - Without outline")
      (description "RES SMD 100K OHM 1% 1/16W 0402")
      (fields
        (field (name "MANUFACTURER") "Yageo")
        (field (name "RESISTANCE") "100kR")
        (field (name "TOLERANCE") "1%")
        (field (name "CREATED BY") "DG")
        (field (name "CHECKED BY") "?")
      )
      (libsource (lib "Yageo") (part "RC0402FR-07100KL"))
    )
    (comp (ref "R28")
      (value "RC0402FR-071ML")
      (footprint "YAGEO-0402:R0402 - Without outline")
      (description "RES SMD 1M OHM 1% 1/16W 0402")
      (fields
        (field (name "MANUFACTURER") "Yageo")
        (field (name "RESISTANCE") "1MR")
        (field (name "TOLERANCE") "1%")
        (field (name "CREATED BY") "D. Gakure")
        (field (name "CHECKED BY") "?")
      )
      (libsource (lib "Yageo") (part "RC0402FR-071ML"))
    )
    (comp (ref "R29")
      (value "RC0402FR-0722KL")
      (footprint "YAGEO-0402:R0402 - Without outline")
      (description "RES SMD 22K OHM 1% 1/16W 0402")
      (fields
        (field (name "MANUFACTURER") "Yageo")
        (field (name "RESISTANCE") "22kR")
        (field (name "TOLERANCE") "1%")
        (field (name "CREATED BY") "DG")
        (field (name "CHECKED BY") "?")
      )
      (libsource (lib "Yageo") (part "RC0402FR-0722KL"))
    )
    (comp (ref "R30")
      (value "RC0402FR-07330KL")
      (footprint "YAGEO-0402:R0402 - without outline")
      (description "RES SMD 330K OHM 1% 1/16W 0402")
      (fields
        (field (name "MANUFACTURER") "Yageo")
        (field (name "RESISTANCE") "330kR")
        (field (name "TOLERANCE") "1%")
        (field (name "CREATED BY") "D Gakure")
        (field (name "CHECKED BY") "?")
      )
      (libsource (lib "Yageo") (part "RC0402FR-07330KL"))
    )
    (comp (ref "SW1")
      (value "~")
      (footprint "USAKRO-UK-B0267-SP25Y")
      (description "SWITCH TACTILE SSPST 50mA @ 12VDC")
      (fields
        (field (name "MANUFACTURER") "USAKRO")
        (field (name "MANUFACTURER PART NUMBER") "UK-B0267-SP25Y")
      )
      (libsource (lib "Usakro") (part "UK-B0267-SP25Y"))
    )
    (comp (ref "U1")
      (value "~")
      (footprint "MICRONE-SOT23-5:MICRONE-SOT23-5")
      (description "6V 260mV @ 200mA(typ) - - Fixed 3.3V SOT-23-5 Linear Voltage Regulators (LDO) ROHS")
      (fields
        (field (name "MANUFACTURER") "MICRONE (Nanjing Micro One Elec)")
        (field (name "MANUFACTURER PART NUMBER") "ME6211C33M5G-N")
        (field (name "CREATED") "DG")
      )
      (libsource (lib "MICRONE(NanjingMicroOneElec)") (part "ME6211C33M5G-N"))
    )
    (comp (ref "U2")
      (value "TPS2553DBVR")
      (footprint "TI-TPS2553 - without_outline")
      (description "IC PWR SWITCH N-CHAN 1:1 SOT23-6")
      (fields
        (field (name "MANUFACTURER") "Texas Instruments")
        (field (name "MANUFACTURER PART NUMBER") "TPS2553DBVR")
      )
      (libsource (lib "TexasInstruments") (part "TPS2553DBVR"))
    )
    (comp (ref "U3")
      (value "~")
      (footprint "RP2040:RP2040-SAFER-VIAS-0.15mm")
      (description "QFN-56_7x7 MCU")
      (fields (field (name "MANUFACTURER") "Raspberry Pi") (field (name "MANUFACTURER PART NUMBER") "RP2040"))
      (libsource (lib "RaspberryPi") (part "RP2040"))
    )
    (comp (ref "U4")
      (value "~")
      (footprint "8-SOIC")
      (description "FLASH - NOR Memory IC 32Mb (4M x 8) SPI - Quad I/O 133 MHz 8-SOIC")
      (fields
        (field (name "MANUFACTURER") "Winbond")
        (field (name "MANUFACTURER PART NUMBER") "W25Q32JVSSIQ")
      )
      (libsource (lib "WinbondElectronics") (part "W25Q32JVSSIQ"))
    )
    (comp (ref "X1")
      (value "generic SMD xtal 3.2x2.5mm")
      (footprint "generic-crystal:generic xtal 3.2x2.5")
      (description "Generic SMD xtal 3.2x2.5mm")
      (fields
        (field (name "FREQUENCY") "12MHz")
        (field (name "LOADING CAPACITANCE") "12pF")
        (field (name "MANUFACTURER") "Multicomp")
        (field (name "MANUFACTURER PART NUMBER") "2853916")
      )
      (libsource (lib "generic-crystal") (part "generic SMD xtal 3.2x2.5mm"))
    )
  )
  (nets
    (net (code "1") (name "/CC1") (class "Default")
      (node (ref "J3") (pin "A5") (pinfunction "CC1_A5") (pintype "passive"))
      (node (ref "R15") (pin "1") (pinfunction "1_1") (pintype "passive"))
    )
    (net (code "2") (name "/CC2") (class "Default")
      (node (ref "J3") (pin "B5") (pinfunction "CC2_B5") (pintype "passive"))
      (node (ref "R14") (pin "1") (pinfunction "1_1") (pintype "passive"))
    )
    (net (code "3") (name "/GPIO0") (class "Default")
      (node (ref "J6") (pin "18") (pinfunction "17_18") (pintype "passive"))
      (node (ref "U3") (pin "2") (pinfunction "GPIO0_2") (pintype "passive"))
    )
    (net (code "4") (name "/GPIO1") (class "Default")
      (node (ref "J6") (pin "16") (pinfunction "15_16") (pintype "passive"))
      (node (ref "U3") (pin "3") (pinfunction "GPIO1_3") (pintype "passive"))
    )
    (net (code "5") (name "/GPIO2") (class "Default")
      (node (ref "J6") (pin "22") (pinfunction "21_22") (pintype "passive"))
      (node (ref "R25") (pin "2") (pinfunction "2_2") (pintype "passive"))
    )
    (net (code "6") (name "/GPIO3") (class "Default")
      (node (ref "J6") (pin "20") (pinfunction "19_20") (pintype "passive"))
      (node (ref "R26") (pin "2") (pinfunction "2_2") (pintype "passive"))
    )
    (net (code "7") (name "/GPIO4") (class "Default")
      (node (ref "J6") (pin "14") (pinfunction "13_14") (pintype "passive"))
      (node (ref "U3") (pin "6") (pinfunction "GPIO4_6") (pintype "passive"))
    )
    (net (code "8") (name "/GPIO5") (class "Default")
      (node (ref "J6") (pin "12") (pinfunction "11_12") (pintype "passive"))
      (node (ref "U3") (pin "7") (pinfunction "GPIO5_7") (pintype "passive"))
    )
    (net (code "9") (name "/GPIO6") (class "Default")
      (node (ref "J6") (pin "10") (pinfunction "9_10") (pintype "passive"))
      (node (ref "U3") (pin "8") (pinfunction "GPIO6_8") (pintype "passive"))
    )
    (net (code "10") (name "/GPIO7") (class "Default")
      (node (ref "J6") (pin "8") (pinfunction "7_8") (pintype "passive"))
      (node (ref "U3") (pin "9") (pinfunction "GPIO7_9") (pintype "passive"))
    )
    (net (code "11") (name "/GPIO10") (class "Default")
      (node (ref "U3") (pin "13") (pinfunction "GPIO10_13") (pintype "passive"))
    )
    (net (code "12") (name "/GPIO24") (class "Default")
      (node (ref "J5") (pin "5") (pinfunction "5_5") (pintype "passive"))
      (node (ref "U3") (pin "36") (pinfunction "GPIO24_36") (pintype "passive"))
    )
    (net (code "13") (name "/GPIO25") (class "Default")
      (node (ref "J5") (pin "7") (pinfunction "7_7") (pintype "passive"))
      (node (ref "U3") (pin "37") (pinfunction "GPIO25_37") (pintype "passive"))
    )
    (net (code "14") (name "/GPIO26") (class "Default")
      (node (ref "J5") (pin "9") (pinfunction "9_9") (pintype "passive"))
      (node (ref "U3") (pin "38") (pinfunction "GPIO26_ADC0_38") (pintype "passive"))
    )
    (net (code "15") (name "/GPIO27") (class "Default")
      (node (ref "J5") (pin "11") (pinfunction "11_11") (pintype "passive"))
      (node (ref "U3") (pin "39") (pinfunction "GPIO27_ADC1_39") (pintype "passive"))
    )
    (net (code "16") (name "/GPIO28") (class "Default")
      (node (ref "J5") (pin "13") (pinfunction "13_13") (pintype "passive"))
      (node (ref "U3") (pin "40") (pinfunction "GPIO28_ADC2_40") (pintype "passive"))
    )
    (net (code "17") (name "/GPIO29") (class "Default")
      (node (ref "J5") (pin "15") (pinfunction "15_15") (pintype "passive"))
      (node (ref "U3") (pin "41") (pinfunction "GPIO29_ADC3_41") (pintype "passive"))
    )
    (net (code "18") (name "/ILIM_DET") (class "Default")
      (node (ref "C22") (pin "2") (pinfunction "2_2") (pintype "passive"))
      (node (ref "R20") (pin "1") (pinfunction "1_1") (pintype "passive"))
      (node (ref "R22") (pin "2") (pinfunction "2_2") (pintype "passive"))
      (node (ref "U3") (pin "15") (pinfunction "GPIO12_15") (pintype "passive"))
    )
    (net (code "19") (name "/ILIM_EN") (class "Default")
      (node (ref "C28") (pin "2") (pinfunction "2_2") (pintype "passive"))
      (node (ref "U3") (pin "34") (pinfunction "GPIO22_34") (pintype "passive"))
    )
    (net (code "20") (name "/JD_DATA") (class "Default")
      (node (ref "D2") (pin "1") (pinfunction "K_1") (pintype "passive"))
      (node (ref "EC1") (pin "1") (pinfunction "D_1") (pintype "passive"))
      (node (ref "FB1") (pin "1") (pinfunction "1_1") (pintype "passive"))
      (node (ref "J6") (pin "2") (pinfunction "1_2") (pintype "passive"))
      (node (ref "MH1") (pin "1") (pinfunction "1_1") (pintype "passive"))
    )
    (net (code "21") (name "/JD_DATA_MCU") (class "Default")
      (node (ref "D1") (pin "3") (pinfunction "K_3") (pintype "passive"))
      (node (ref "R1") (pin "2") (pinfunction "2_2") (pintype "passive"))
      (node (ref "U3") (pin "12") (pinfunction "GPIO9_12") (pintype "passive"))
    )
    (net (code "22") (name "/JD_RGB_B") (class "Default")
      (node (ref "R11") (pin "2") (pinfunction "2_2") (pintype "passive"))
      (node (ref "U3") (pin "18") (pinfunction "GPIO15_18") (pintype "passive"))
    )
    (net (code "23") (name "/JD_RGB_G") (class "Default")
      (node (ref "R12") (pin "2") (pinfunction "2_2") (pintype "passive"))
      (node (ref "U3") (pin "17") (pinfunction "GPIO14_17") (pintype "passive"))
    )
    (net (code "24") (name "/JD_RGB_R") (class "Default")
      (node (ref "R13") (pin "2") (pinfunction "2_2") (pintype "passive"))
      (node (ref "U3") (pin "27") (pinfunction "GPIO16_27") (pintype "passive"))
    )
    (net (code "25") (name "/MCU_QSPI_SCLK") (class "Default")
      (node (ref "U3") (pin "52") (pinfunction "QSPI_SCLK_52") (pintype "passive"))
      (node (ref "U4") (pin "6") (pinfunction "CLK_6") (pintype "passive"))
    )
    (net (code "26") (name "/MCU_QSPI_SD0") (class "Default")
      (node (ref "U3") (pin "53") (pinfunction "QSPI_SD0_53") (pintype "passive"))
      (node (ref "U4") (pin "5") (pinfunction "DI(IO0)_5") (pintype "passive"))
    )
    (net (code "27") (name "/MCU_QSPI_SD1") (class "Default")
      (node (ref "U3") (pin "55") (pinfunction "QSPI_SD1_55") (pintype "passive"))
      (node (ref "U4") (pin "2") (pinfunction "DO(IO1)_2") (pintype "passive"))
    )
    (net (code "28") (name "/MCU_QSPI_SD2") (class "Default")
      (node (ref "U3") (pin "54") (pinfunction "QSPI_SD2_54") (pintype "passive"))
      (node (ref "U4") (pin "3") (pinfunction "~{WP}(IO2)_3") (pintype "passive"))
    )
    (net (code "29") (name "/MCU_QSPI_SD3") (class "Default")
      (node (ref "U3") (pin "51") (pinfunction "QSPI_SD3_51") (pintype "passive"))
      (node (ref "U4") (pin "7") (pinfunction "~{HOLD/RESET}(IO3)_7") (pintype "passive"))
    )
    (net (code "30") (name "/MCU_QSPI_SS") (class "Default")
      (node (ref "R7") (pin "2") (pinfunction "2_2") (pintype "passive"))
      (node (ref "R8") (pin "1") (pinfunction "1_1") (pintype "passive"))
      (node (ref "U3") (pin "56") (pinfunction "QSPI_SS_56") (pintype "passive"))
      (node (ref "U4") (pin "1") (pinfunction "~{CS}_1") (pintype "passive"))
    )
    (net (code "31") (name "/MCU_USB_D_N") (class "Default")
      (node (ref "R4") (pin "1") (pinfunction "1_1") (pintype "passive"))
      (node (ref "U3") (pin "46") (pinfunction "USB_DM_46") (pintype "passive"))
    )
    (net (code "32") (name "/MCU_USB_D_P") (class "Default")
      (node (ref "R3") (pin "1") (pinfunction "1_1") (pintype "passive"))
      (node (ref "U3") (pin "47") (pinfunction "USB_DP_47") (pintype "passive"))
    )
    (net (code "33") (name "/PD_STATUS") (class "Default")
      (node (ref "R16") (pin "1") (pinfunction "1_1") (pintype "passive"))
      (node (ref "U3") (pin "16") (pinfunction "GPIO13_16") (pintype "passive"))
    )
    (net (code "34") (name "/SWCLK") (class "Default")
      (node (ref "J1") (pin "4") (pinfunction "SWCLK_4") (pintype "passive"))
      (node (ref "U3") (pin "24") (pinfunction "SWCLK_24") (pintype "passive"))
    )
    (net (code "35") (name "/SWDIO") (class "Default")
      (node (ref "J1") (pin "2") (pinfunction "SWDIO_2") (pintype "passive"))
      (node (ref "U3") (pin "25") (pinfunction "SWD_25") (pintype "passive"))
    )
    (net (code "36") (name "/USB_D_N") (class "Default")
      (node (ref "D5") (pin "1") (pinfunction "K_1") (pintype "passive"))
      (node (ref "J3") (pin "A7") (pinfunction "D-_A7") (pintype "passive"))
      (node (ref "J3") (pin "B7") (pinfunction "D-_B7") (pintype "passive"))
      (node (ref "J5") (pin "19") (pinfunction "19_19") (pintype "passive"))
      (node (ref "R4") (pin "2") (pinfunction "2_2") (pintype "passive"))
    )
    (net (code "37") (name "/USB_D_P") (class "Default")
      (node (ref "D4") (pin "1") (pinfunction "K_1") (pintype "passive"))
      (node (ref "J3") (pin "A6") (pinfunction "D+_A6") (pintype "passive"))
      (node (ref "J3") (pin "B6") (pinfunction "D+_B6") (pintype "passive"))
      (node (ref "J5") (pin "17") (pinfunction "17_17") (pintype "passive"))
      (node (ref "R3") (pin "2") (pinfunction "2_2") (pintype "passive"))
    )
    (net (code "38") (name "/USB_PBKA") (class "Default")
      (node (ref "C29") (pin "1") (pinfunction "1_1") (pintype "passive"))
      (node (ref "U3") (pin "11") (pinfunction "GPIO8_11") (pintype "passive"))
    )
    (net (code "39") (name "/VUSB_DET") (class "Default")
      (node (ref "C23") (pin "2") (pinfunction "2_2") (pintype "passive"))
      (node (ref "R21") (pin "1") (pinfunction "1_1") (pintype "passive"))
      (node (ref "R23") (pin "2") (pinfunction "2_2") (pintype "passive"))
      (node (ref "U3") (pin "14") (pinfunction "GPIO11_14") (pintype "passive"))
    )
    (net (code "40") (name "/XIN") (class "Default")
      (node (ref "C20") (pin "1") (pinfunction "1_1") (pintype "passive"))
      (node (ref "U3") (pin "20") (pinfunction "XIN_20") (pintype "passive"))
      (node (ref "X1") (pin "3") (pinfunction "3_3") (pintype "passive"))
    )
    (net (code "41") (name "/XOUT") (class "Default")
      (node (ref "R9") (pin "2") (pinfunction "2_2") (pintype "passive"))
      (node (ref "U3") (pin "21") (pinfunction "XOUT_21") (pintype "passive"))
    )
    (net (code "42") (name "/~{BOOT}") (class "Default")
      (node (ref "Q1") (pin "1") (pinfunction "E1_1") (pintype "passive"))
      (node (ref "R8") (pin "2") (pinfunction "2_2") (pintype "passive"))
    )
    (net (code "43") (name "/~{ILIM_HI}") (class "Default")
      (node (ref "R5") (pin "1") (pinfunction "1_1") (pintype "passive"))
      (node (ref "U3") (pin "29") (pinfunction "GPIO18_29") (pintype "passive"))
    )
    (net (code "44") (name "/~{RESET}") (class "Default")
      (node (ref "J1") (pin "5") (pinfunction "RESET_5") (pintype "passive"))
      (node (ref "J5") (pin "3") (pinfunction "5_3") (pintype "passive"))
      (node (ref "Q1") (pin "4") (pinfunction "E2_4") (pintype "passive"))
      (node (ref "R24") (pin "1") (pinfunction "1_1") (pintype "passive"))
      (node (ref "SW1") (pin "2") (pinfunction "2_2") (pintype "passive"))
      (node (ref "U3") (pin "26") (pinfunction "RUN_26") (pintype "passive"))
    )
    (net (code "45") (name "1V1") (class "Default")
      (node (ref "C13") (pin "2") (pinfunction "2_2") (pintype "passive"))
      (node (ref "C14") (pin "2") (pinfunction "2_2") (pintype "passive"))
      (node (ref "C15") (pin "2") (pinfunction "2_2") (pintype "passive"))
      (node (ref "U3") (pin "23") (pinfunction "DVDD_23") (pintype "passive"))
      (node (ref "U3") (pin "45") (pinfunction "VREG_VOUT_45") (pintype "passive"))
      (node (ref "U3") (pin "50") (pinfunction "DVDD_50") (pintype "passive"))
    )
    (net (code "46") (name "3V3") (class "Default")
      (node (ref "C10") (pin "2") (pinfunction "2_2") (pintype "passive"))
      (node (ref "C11") (pin "2") (pinfunction "2_2") (pintype "passive"))
      (node (ref "C12") (pin "2") (pinfunction "2_2") (pintype "passive"))
      (node (ref "C19") (pin "2") (pinfunction "2_2") (pintype "passive"))
      (node (ref "C3") (pin "2") (pinfunction "2_2") (pintype "passive"))
      (node (ref "C7") (pin "2") (pinfunction "2_2") (pintype "passive"))
      (node (ref "C8") (pin "2") (pinfunction "2_2") (pintype "passive"))
      (node (ref "C9") (pin "2") (pinfunction "2_2") (pintype "passive"))
      (node (ref "D1") (pin "2") (pinfunction "K_2") (pintype "passive"))
      (node (ref "D9") (pin "1") (pinfunction "A_1") (pintype "passive"))
      (node (ref "J1") (pin "1") (pinfunction "VCC_1") (pintype "passive"))
      (node (ref "J6") (pin "6") (pinfunction "5_6") (pintype "passive"))
      (node (ref "R7") (pin "1") (pinfunction "1_1") (pintype "passive"))
      (node (ref "U1") (pin "5") (pinfunction "OUT_5") (pintype "passive"))
      (node (ref "U3") (pin "1") (pinfunction "IOVDD_1") (pintype "passive"))
      (node (ref "U3") (pin "10") (pinfunction "IOVDD_10") (pintype "passive"))
      (node (ref "U3") (pin "22") (pinfunction "IOVDD_22") (pintype "passive"))
      (node (ref "U3") (pin "33") (pinfunction "IOVDD_33") (pintype "passive"))
      (node (ref "U3") (pin "42") (pinfunction "IOVDD_42") (pintype "passive"))
      (node (ref "U3") (pin "43") (pinfunction "ADC_AVDD_43") (pintype "passive"))
      (node (ref "U3") (pin "44") (pinfunction "VREG_IN_44") (pintype "passive"))
      (node (ref "U3") (pin "48") (pinfunction "USB_VDD_48") (pintype "passive"))
      (node (ref "U3") (pin "49") (pinfunction "IOVDD_49") (pintype "passive"))
      (node (ref "U4") (pin "8") (pinfunction "VCC_8") (pintype "power_in"))
    )
    (net (code "47") (name "GND") (class "Default")
      (node (ref "C1") (pin "1") (pinfunction "1_1") (pintype "passive"))
      (node (ref "C10") (pin "1") (pinfunction "1_1") (pintype "passive"))
      (node (ref "C11") (pin "1") (pinfunction "1_1") (pintype "passive"))
      (node (ref "C12") (pin "1") (pinfunction "1_1") (pintype "passive"))
      (node (ref "C13") (pin "1") (pinfunction "1_1") (pintype "passive"))
      (node (ref "C14") (pin "1") (pinfunction "1_1") (pintype "passive"))
      (node (ref "C15") (pin "1") (pinfunction "1_1") (pintype "passive"))
      (node (ref "C19") (pin "1") (pinfunction "1_1") (pintype "passive"))
      (node (ref "C2") (pin "1") (pinfunction "1_1") (pintype "passive"))
      (node (ref "C20") (pin "2") (pinfunction "2_2") (pintype "passive"))
      (node (ref "C21") (pin "2") (pinfunction "2_2") (pintype "passive"))
      (node (ref "C22") (pin "1") (pinfunction "1_1") (pintype "passive"))
      (node (ref "C23") (pin "1") (pinfunction "1_1") (pintype "passive"))
      (node (ref "C24") (pin "1") (pinfunction "1_1") (pintype "passive"))
      (node (ref "C27") (pin "1") (pinfunction "1_1") (pintype "passive"))
      (node (ref "C3") (pin "1") (pinfunction "1_1") (pintype "passive"))
      (node (ref "C4") (pin "1") (pinfunction "1_1") (pintype "passive"))
      (node (ref "C5") (pin "1") (pinfunction "1_1") (pintype "passive"))
      (node (ref "C6") (pin "1") (pinfunction "1_1") (pintype "passive"))
      (node (ref "C7") (pin "1") (pinfunction "1_1") (pintype "passive"))
      (node (ref "C8") (pin "1") (pinfunction "1_1") (pintype "passive"))
      (node (ref "C9") (pin "1") (pinfunction "1_1") (pintype "passive"))
      (node (ref "D1") (pin "1") (pinfunction "A_1") (pintype "passive"))
      (node (ref "D13") (pin "1") (pinfunction "A_1") (pintype "passive"))
      (node (ref "D2") (pin "2") (pinfunction "A_2") (pintype "passive"))
      (node (ref "D3") (pin "2") (pinfunction "A_2") (pintype "passive"))
      (node (ref "D4") (pin "2") (pinfunction "A_2") (pintype "passive"))
      (node (ref "D5") (pin "2") (pinfunction "A_2") (pintype "passive"))
      (node (ref "D6") (pin "2") (pinfunction "A_2") (pintype "passive"))
      (node (ref "EC1") (pin "2") (pinfunction "G_2") (pintype "passive"))
      (node (ref "J1") (pin "3") (pinfunction "GND_3") (pintype "passive"))
      (node (ref "J3") (pin "A1") (pinfunction "GND_A1") (pintype "passive"))
      (node (ref "J3") (pin "A12") (pinfunction "GND_A12") (pintype "passive"))
      (node (ref "J3") (pin "B1") (pinfunction "GND_B1") (pintype "passive"))
      (node (ref "J3") (pin "B12") (pinfunction "GND_B12") (pintype "passive"))
      (node (ref "J5") (pin "23") (pinfunction "23_23") (pintype "passive"))
      (node (ref "J6") (pin "24") (pinfunction "23_24") (pintype "passive"))
      (node (ref "MH2") (pin "1") (pinfunction "1_1") (pintype "passive"))
      (node (ref "MH4") (pin "1") (pinfunction "1_1") (pintype "passive"))
      (node (ref "Q1") (pin "3") (pinfunction "C2_3") (pintype "passive"))
      (node (ref "Q1") (pin "6") (pinfunction "C1_6") (pintype "passive"))
      (node (ref "Q2") (pin "2") (pinfunction "S_2") (pintype "passive"))
      (node (ref "R14") (pin "2") (pinfunction "2_2") (pintype "passive"))
      (node (ref "R15") (pin "2") (pinfunction "2_2") (pintype "passive"))
      (node (ref "R17") (pin "2") (pinfunction "2_2") (pintype "passive"))
      (node (ref "R22") (pin "1") (pinfunction "1_1") (pintype "passive"))
      (node (ref "R23") (pin "1") (pinfunction "1_1") (pintype "passive"))
      (node (ref "R27") (pin "1") (pinfunction "1_1") (pintype "passive"))
      (node (ref "R30") (pin "2") (pinfunction "2_2") (pintype "passive"))
      (node (ref "R6") (pin "1") (pinfunction "1_1") (pintype "passive"))
      (node (ref "SW1") (pin "3") (pinfunction "3_3") (pintype "passive"))
      (node (ref "SW1") (pin "4") (pinfunction "4_4") (pintype "passive"))
      (node (ref "U1") (pin "2") (pinfunction "GND_2") (pintype "passive"))
      (node (ref "U2") (pin "2") (pinfunction "GND_2") (pintype "passive"))
      (node (ref "U3") (pin "19") (pinfunction "TESTEN_19") (pintype "passive"))
      (node (ref "U3") (pin "57") (pinfunction "EXP_57") (pintype "passive"))
      (node (ref "U4") (pin "4") (pinfunction "GND_4") (pintype "power_in"))
      (node (ref "X1") (pin "2") (pinfunction "2_2") (pintype "passive"))
      (node (ref "X1") (pin "4") (pinfunction "4_4") (pintype "passive"))
    )
    (net (code "48") (name "ILIM_OUT") (class "Default")
      (node (ref "C6") (pin "2") (pinfunction "2_2") (pintype "passive"))
      (node (ref "D10") (pin "2") (pinfunction "A_2") (pintype "passive"))
      (node (ref "D8") (pin "2") (pinfunction "A_2") (pintype "passive"))
      (node (ref "R20") (pin "2") (pinfunction "2_2") (pintype "passive"))
      (node (ref "U2") (pin "6") (pinfunction "OUT_6") (pintype "passive"))
    )
    (net (code "49") (name "JD_PWR") (class "Default")
      (node (ref "D10") (pin "1") (pinfunction "K_1") (pintype "passive"))
      (node (ref "D12") (pin "2") (pinfunction "A_2") (pintype "passive"))
      (node (ref "D3") (pin "1") (pinfunction "K_1") (pintype "passive"))
      (node (ref "EC1") (pin "3") (pinfunction "P_3") (pintype "passive"))
      (node (ref "J5") (pin "1") (pinfunction "1_1") (pintype "passive"))
      (node (ref "MH3") (pin "1") (pinfunction "1_1") (pintype "passive"))
    )
    (net (code "50") (name "Net-(C1-Pad2)") (class "Default")
      (node (ref "C1") (pin "2") (pinfunction "2_2") (pintype "passive"))
      (node (ref "FB1") (pin "2") (pinfunction "2_2") (pintype "passive"))
      (node (ref "R1") (pin "1") (pinfunction "1_1") (pintype "passive"))
    )
    (net (code "51") (name "Net-(C21-Pad1)") (class "Default")
      (node (ref "C21") (pin "1") (pinfunction "1_1") (pintype "passive"))
      (node (ref "R9") (pin "1") (pinfunction "1_1") (pintype "passive"))
      (node (ref "X1") (pin "1") (pinfunction "1_1") (pintype "passive"))
    )
    (net (code "52") (name "Net-(C29-Pad2)") (class "Default")
      (node (ref "C29") (pin "2") (pinfunction "2_2") (pintype "passive"))
      (node (ref "R29") (pin "2") (pinfunction "2_2") (pintype "passive"))
    )
    (net (code "53") (name "Net-(D8-K)") (class "Default")
      (node (ref "D8") (pin "1") (pinfunction "K_1") (pintype "passive"))
      (node (ref "R16") (pin "2") (pinfunction "2_2") (pintype "passive"))
      (node (ref "R17") (pin "1") (pinfunction "1_1") (pintype "passive"))
    )
    (net (code "54") (name "Net-(D9-B)") (class "Default")
      (node (ref "D9") (pin "4") (pinfunction "B_4") (pintype "passive"))
      (node (ref "R11") (pin "1") (pinfunction "1_1") (pintype "passive"))
    )
    (net (code "55") (name "Net-(D9-G)") (class "Default")
      (node (ref "D9") (pin "3") (pinfunction "G_3") (pintype "passive"))
      (node (ref "R12") (pin "1") (pinfunction "1_1") (pintype "passive"))
    )
    (net (code "56") (name "Net-(D9-R)") (class "Default")
      (node (ref "D9") (pin "2") (pinfunction "R_2") (pintype "passive"))
      (node (ref "R13") (pin "1") (pinfunction "1_1") (pintype "passive"))
    )
    (net (code "57") (name "Net-(D13A-K)") (class "Default")
      (node (ref "C28") (pin "1") (pinfunction "1_1") (pintype "passive"))
      (node (ref "D13") (pin "3") (pinfunction "K_3") (pintype "passive"))
    )
    (net (code "58") (name "Net-(D13B-K)") (class "Default")
      (node (ref "D13") (pin "2") (pinfunction "K_2") (pintype "passive"))
      (node (ref "R2") (pin "1") (pinfunction "1_1") (pintype "passive"))
      (node (ref "R27") (pin "2") (pinfunction "2_2") (pintype "passive"))
    )
    (net (code "59") (name "Net-(Q1A-B1)") (class "Default")
      (node (ref "C24") (pin "2") (pinfunction "2_2") (pintype "passive"))
      (node (ref "Q1") (pin "2") (pinfunction "B1_2") (pintype "passive"))
      (node (ref "R24") (pin "2") (pinfunction "2_2") (pintype "passive"))
    )
    (net (code "60") (name "Net-(Q1B-B2)") (class "Default")
      (node (ref "C27") (pin "2") (pinfunction "2_2") (pintype "passive"))
      (node (ref "Q1") (pin "5") (pinfunction "B2_5") (pintype "passive"))
      (node (ref "R28") (pin "2") (pinfunction "2_2") (pintype "passive"))
    )
    (net (code "61") (name "Net-(Q2-D)") (class "Default")
      (node (ref "Q2") (pin "3") (pinfunction "D_3") (pintype "passive"))
      (node (ref "R18") (pin "1") (pinfunction "1_1") (pintype "passive"))
    )
    (net (code "62") (name "Net-(Q2-G)") (class "Default")
      (node (ref "Q2") (pin "1") (pinfunction "G_1") (pintype "passive"))
      (node (ref "R29") (pin "1") (pinfunction "1_1") (pintype "passive"))
      (node (ref "R30") (pin "1") (pinfunction "1_1") (pintype "passive"))
    )
    (net (code "63") (name "Net-(U2-EN)") (class "Default")
      (node (ref "C5") (pin "2") (pinfunction "2_2") (pintype "passive"))
      (node (ref "R2") (pin "2") (pinfunction "2_2") (pintype "passive"))
      (node (ref "U2") (pin "3") (pinfunction "EN_3") (pintype "passive"))
      (node (ref "U2") (pin "4") (pinfunction "~{FAULT}_4") (pintype "passive"))
    )
    (net (code "64") (name "Net-(U2-ILIM)") (class "Default")
      (node (ref "R5") (pin "2") (pinfunction "2_2") (pintype "passive"))
      (node (ref "R6") (pin "2") (pinfunction "2_2") (pintype "passive"))
      (node (ref "U2") (pin "5") (pinfunction "ILIM_5") (pintype "passive"))
    )
    (net (code "65") (name "Net-(U3-GPIO2)") (class "Default")
      (node (ref "R25") (pin "1") (pinfunction "1_1") (pintype "passive"))
      (node (ref "U3") (pin "4") (pinfunction "GPIO2_4") (pintype "passive"))
    )
    (net (code "66") (name "Net-(U3-GPIO3)") (class "Default")
      (node (ref "R26") (pin "1") (pinfunction "1_1") (pintype "passive"))
      (node (ref "U3") (pin "5") (pinfunction "GPIO3_5") (pintype "passive"))
    )
    (net (code "67") (name "VCOMB") (class "Default")
      (node (ref "C2") (pin "2") (pinfunction "2_2") (pintype "passive"))
      (node (ref "D11") (pin "1") (pinfunction "K_1") (pintype "passive"))
      (node (ref "D12") (pin "1") (pinfunction "K_1") (pintype "passive"))
      (node (ref "R28") (pin "1") (pinfunction "1_1") (pintype "passive"))
      (node (ref "U1") (pin "1") (pinfunction "IN_1") (pintype "passive"))
      (node (ref "U1") (pin "3") (pinfunction "EN_3") (pintype "passive"))
    )
    (net (code "68") (name "VUSB") (class "Default")
      (node (ref "C4") (pin "2") (pinfunction "2_2") (pintype "passive"))
      (node (ref "D11") (pin "2") (pinfunction "A_2") (pintype "passive"))
      (node (ref "D6") (pin "1") (pinfunction "K_1") (pintype "passive"))
      (node (ref "J3") (pin "A4") (pinfunction "VBUS_A4") (pintype "passive"))
      (node (ref "J3") (pin "A9") (pinfunction "VBUS_A9") (pintype "passive"))
      (node (ref "J3") (pin "B4") (pinfunction "VBUS_B4") (pintype "passive"))
      (node (ref "J3") (pin "B9") (pinfunction "VBUS_B9") (pintype "passive"))
      (node (ref "J5") (pin "21") (pinfunction "21_21") (pintype "passive"))
      (node (ref "R18") (pin "2") (pinfunction "2_2") (pintype "passive"))
      (node (ref "R21") (pin "2") (pinfunction "2_2") (pintype "passive"))
      (node (ref "U2") (pin "1") (pinfunction "IN_1") (pintype "passive"))
    )
    (net (code "69") (name "unconnected-(J3-SBU1-PadA8)") (class "Default")
      (node (ref "J3") (pin "A8") (pinfunction "SBU1_A8") (pintype "passive+no_connect"))
    )
    (net (code "70") (name "unconnected-(J3-SBU2-PadB8)") (class "Default")
      (node (ref "J3") (pin "B8") (pinfunction "SBU2_B8") (pintype "passive+no_connect"))
    )
    (net (code "71") (name "unconnected-(SW1-Pad1)") (class "Default")
      (node (ref "SW1") (pin "1") (pinfunction "1_1") (pintype "passive+no_connect"))
    )
    (net (code "72") (name "unconnected-(U3-GPIO17-Pad28)") (class "Default")
      (node (ref "U3") (pin "28") (pinfunction "GPIO17_28") (pintype "passive+no_connect"))
    )
    (net (code "73") (name "unconnected-(U3-GPIO19-Pad30)") (class "Default")
      (node (ref "U3") (pin "30") (pinfunction "GPIO19_30") (pintype "passive+no_connect"))
    )
    (net (code "74") (name "unconnected-(U3-GPIO20-Pad31)") (class "Default")
      (node (ref "U3") (pin "31") (pinfunction "GPIO20_31") (pintype "passive+no_connect"))
    )
    (net (code "75") (name "unconnected-(U3-GPIO21-Pad32)") (class "Default")
      (node (ref "U3") (pin "32") (pinfunction "GPIO21_32") (pintype "passive+no_connect"))
    )
    (net (code "76") (name "unconnected-(U3-GPIO23-Pad35)") (class "Default")
      (node (ref "U3") (pin "35") (pinfunction "GPIO23_35") (pintype "passive+no_connect"))
    )
  )
)
